# Proj15.net
KiCad netlist of a schematic drawn in EAGLE
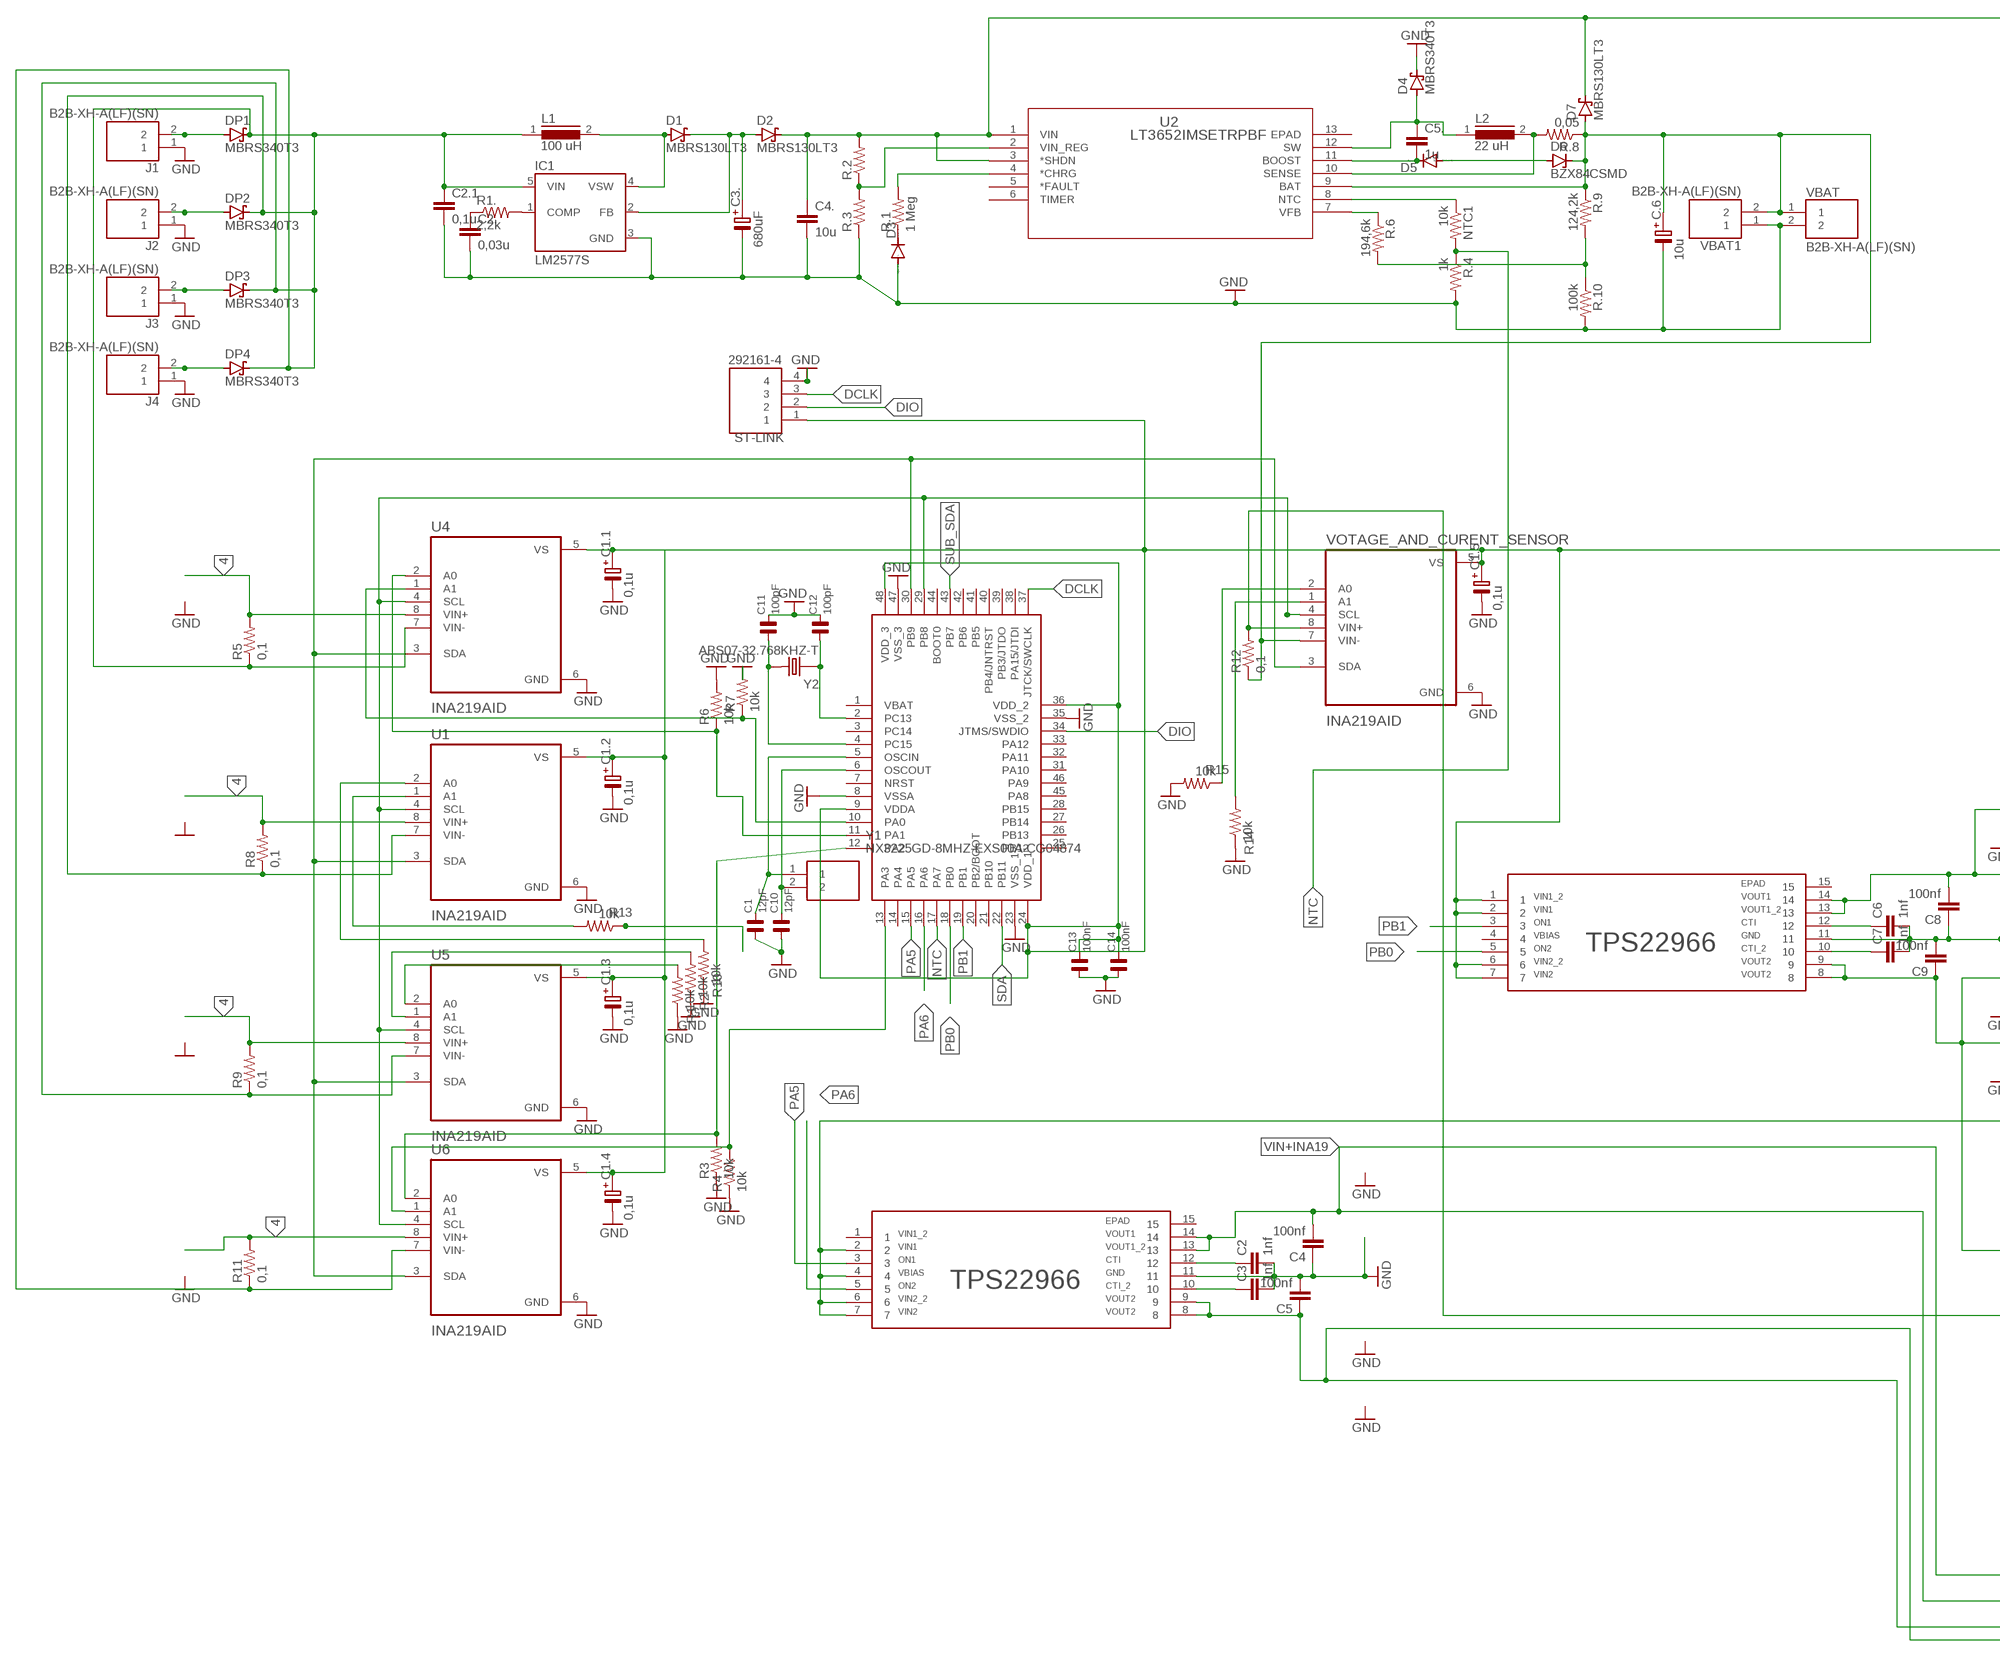
[diagram p0: schematic, sheet 1, part 1 of 2]
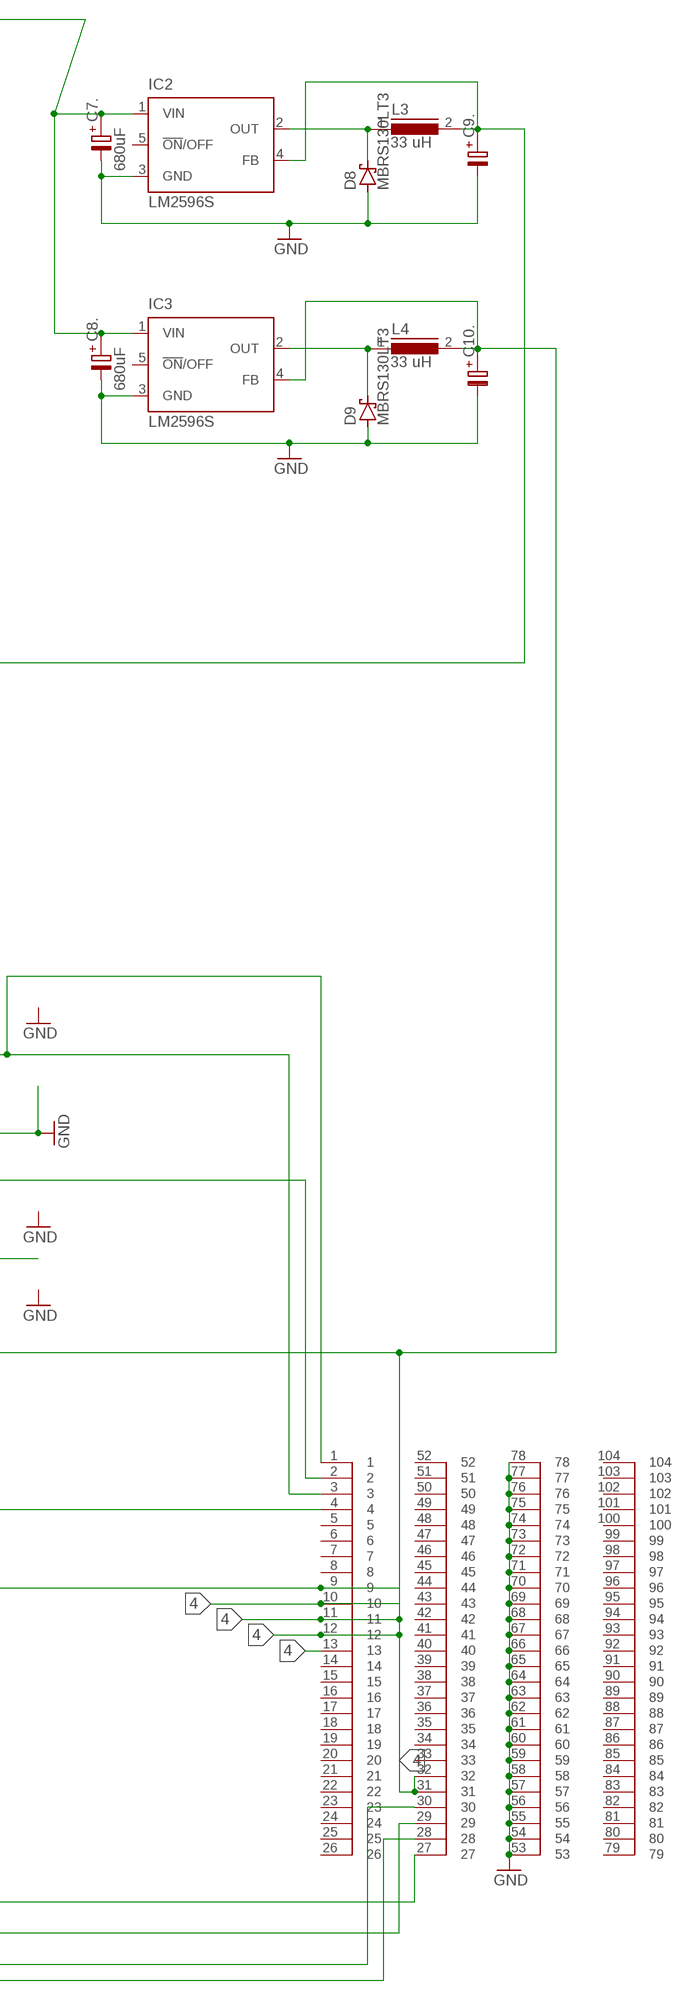
[diagram p1: schematic, sheet 1, part 2 of 2]

(export (version "E")
  (design (tool "Eeschema 10.0.6"))
  (components
    (comp (ref "C.6")
      (value "10u")
      (footprint "eagle-import:TE-D-7343")
      (libsource (lib "eagle-import") (part "C-PR-SMD-TE-D"))
    )
    (comp (ref "C1")
      (value "12pF")
      (footprint "eagle-import:0805")
      (libsource (lib "eagle-import") (part "C0805"))
    )
    (comp (ref "C1.1")
      (value "0,1u")
      (footprint "eagle-import:TE-D-7343")
      (libsource (lib "eagle-import") (part "C-PR-SMD-TE-D"))
    )
    (comp (ref "C1.2")
      (value "0,1u")
      (footprint "eagle-import:TE-D-7343")
      (libsource (lib "eagle-import") (part "C-PR-SMD-TE-D"))
    )
    (comp (ref "C1.3")
      (value "0,1u")
      (footprint "eagle-import:TE-D-7343")
      (libsource (lib "eagle-import") (part "C-PR-SMD-TE-D"))
    )
    (comp (ref "C1.4")
      (value "0,1u")
      (footprint "eagle-import:TE-D-7343")
      (libsource (lib "eagle-import") (part "C-PR-SMD-TE-D"))
    )
    (comp (ref "C1.5")
      (value "0,1u")
      (footprint "eagle-import:TE-D-7343")
      (libsource (lib "eagle-import") (part "C-PR-SMD-TE-D"))
    )
    (comp (ref "C2")
      (value "1nf")
      (footprint "eagle-import:C0805")
      (libsource (lib "eagle-import") (part "C-EUC0805"))
    )
    (comp (ref "C2.")
      (value "0,03u")
      (footprint "eagle-import:C1206")
      (libsource (lib "eagle-import") (part "C-EUC1206"))
    )
    (comp (ref "C2.1")
      (value "0,1u")
      (footprint "eagle-import:C1206")
      (libsource (lib "eagle-import") (part "C-EUC1206"))
    )
    (comp (ref "C3")
      (value "1nf")
      (footprint "eagle-import:C0805")
      (libsource (lib "eagle-import") (part "C-EUC0805"))
    )
    (comp (ref "C3.")
      (value "680uF")
      (footprint "eagle-import:TE-D-7343")
      (libsource (lib "eagle-import") (part "C-PR-SMD-TE-D"))
    )
    (comp (ref "C4")
      (value "100nf")
      (footprint "eagle-import:C0805")
      (libsource (lib "eagle-import") (part "C-EUC0805"))
    )
    (comp (ref "C4.")
      (value "10u")
      (footprint "eagle-import:C1206")
      (libsource (lib "eagle-import") (part "C-EUC1206"))
    )
    (comp (ref "C5")
      (value "100nf")
      (footprint "eagle-import:C0805")
      (libsource (lib "eagle-import") (part "C-EUC0805"))
    )
    (comp (ref "C5.")
      (value "1u")
      (footprint "eagle-import:C1206")
      (libsource (lib "eagle-import") (part "C-EUC1206"))
    )
    (comp (ref "C6")
      (value "1nf")
      (footprint "eagle-import:C0805")
      (libsource (lib "eagle-import") (part "C-EUC0805"))
    )
    (comp (ref "C7")
      (value "1nf")
      (footprint "eagle-import:C0805")
      (libsource (lib "eagle-import") (part "C-EUC0805"))
    )
    (comp (ref "C7.")
      (value "680uF")
      (footprint "eagle-import:TE-D-7343")
      (libsource (lib "eagle-import") (part "C-PR-SMD-TE-D"))
    )
    (comp (ref "C8")
      (value "100nf")
      (footprint "eagle-import:C0805")
      (libsource (lib "eagle-import") (part "C-EUC0805"))
    )
    (comp (ref "C8.")
      (value "680uF")
      (footprint "eagle-import:TE-D-7343")
      (libsource (lib "eagle-import") (part "C-PR-SMD-TE-D"))
    )
    (comp (ref "C9")
      (value "100nf")
      (footprint "eagle-import:C0805")
      (libsource (lib "eagle-import") (part "C-EUC0805"))
    )
    (comp (ref "C9.")
      (value "C-PR-SMD-TE-D")
      (footprint "eagle-import:TE-D-7343")
      (libsource (lib "eagle-import") (part "C-PR-SMD-TE-D"))
    )
    (comp (ref "C10")
      (value "12pF")
      (footprint "eagle-import:0805")
      (libsource (lib "eagle-import") (part "C0805"))
    )
    (comp (ref "C10.")
      (value "C-PR-SMD-TE-D")
      (footprint "eagle-import:TE-D-7343")
      (libsource (lib "eagle-import") (part "C-PR-SMD-TE-D"))
    )
    (comp (ref "C11")
      (value "100pF")
      (footprint "eagle-import:0805")
      (libsource (lib "eagle-import") (part "C0805"))
    )
    (comp (ref "C12")
      (value "100pF")
      (footprint "eagle-import:0805")
      (libsource (lib "eagle-import") (part "C0805"))
    )
    (comp (ref "C13")
      (value "100nF")
      (footprint "eagle-import:0805")
      (libsource (lib "eagle-import") (part "C0805"))
    )
    (comp (ref "C14")
      (value "100nF")
      (footprint "eagle-import:0805")
      (libsource (lib "eagle-import") (part "C0805"))
    )
    (comp (ref "D1")
      (value "MBRS130LT3")
      (footprint "eagle-import:SMB")
      (libsource (lib "eagle-import") (part "MBRS130LT3"))
    )
    (comp (ref "D2")
      (value "MBRS130LT3")
      (footprint "eagle-import:SMB")
      (libsource (lib "eagle-import") (part "MBRS130LT3"))
    )
    (comp (ref "D3")
      (value "DIODE-DO214BA")
      (footprint "eagle-import:DO214BA")
      (libsource (lib "eagle-import") (part "DIODE-DO214BA"))
    )
    (comp (ref "D4")
      (value "MBRS340T3")
      (footprint "eagle-import:SMC")
      (libsource (lib "eagle-import") (part "MBRS30T34"))
    )
    (comp (ref "D5")
      (value "DIODE-DO214BA")
      (footprint "eagle-import:DO214BA")
      (libsource (lib "eagle-import") (part "DIODE-DO214BA"))
    )
    (comp (ref "D6")
      (value "BZX84CSMD")
      (footprint "eagle-import:TO236")
      (libsource (lib "eagle-import") (part "BZX84CSMD"))
    )
    (comp (ref "D7")
      (value "MBRS130LT3")
      (footprint "eagle-import:SMB")
      (libsource (lib "eagle-import") (part "MBRS130LT3"))
    )
    (comp (ref "D8")
      (value "MBRS130LT3")
      (footprint "eagle-import:SMB")
      (libsource (lib "eagle-import") (part "MBRS130LT3"))
    )
    (comp (ref "D9")
      (value "MBRS130LT3")
      (footprint "eagle-import:SMB")
      (libsource (lib "eagle-import") (part "MBRS130LT3"))
    )
    (comp (ref "DP1")
      (value "MBRS340T3")
      (footprint "eagle-import:SMC")
      (libsource (lib "eagle-import") (part "MBRS30T34"))
    )
    (comp (ref "DP2")
      (value "MBRS340T3")
      (footprint "eagle-import:SMC")
      (libsource (lib "eagle-import") (part "MBRS30T34"))
    )
    (comp (ref "DP3")
      (value "MBRS340T3")
      (footprint "eagle-import:SMC")
      (libsource (lib "eagle-import") (part "MBRS30T34"))
    )
    (comp (ref "DP4")
      (value "MBRS340T3")
      (footprint "eagle-import:SMC")
      (libsource (lib "eagle-import") (part "MBRS30T34"))
    )
    (comp (ref "IC1")
      (value "LM2577S")
      (footprint "eagle-import:TO263-5")
      (libsource (lib "eagle-import") (part "LM2577S"))
    )
    (comp (ref "IC2")
      (value "LM2596S")
      (footprint "eagle-import:TO263-5")
      (fields (field (name "MF") "NATIONAL SEMICONDUCTOR") (field (name "MPN") "LM2596S-ADJ/NOPB"))
      (libsource (lib "eagle-import") (part "LM2596S"))
    )
    (comp (ref "IC3")
      (value "LM2596S")
      (footprint "eagle-import:TO263-5")
      (fields (field (name "MF") "NATIONAL SEMICONDUCTOR") (field (name "MPN") "LM2596S-ADJ/NOPB"))
      (libsource (lib "eagle-import") (part "LM2596S"))
    )
    (comp (ref "J1")
      (value "B2B-XH-A(LF)(SN)")
      (footprint "eagle-import:JST_B2B-XH-A(LF)(SN)")
      (fields (field (name "MF") "JST Sales"))
      (libsource (lib "eagle-import") (part "B2B-XH-A(LF)(SN)"))
    )
    (comp (ref "J2")
      (value "B2B-XH-A(LF)(SN)")
      (footprint "eagle-import:JST_B2B-XH-A(LF)(SN)")
      (fields (field (name "MF") "JST Sales"))
      (libsource (lib "eagle-import") (part "B2B-XH-A(LF)(SN)"))
    )
    (comp (ref "J3")
      (value "B2B-XH-A(LF)(SN)")
      (footprint "eagle-import:JST_B2B-XH-A(LF)(SN)")
      (fields (field (name "MF") "JST Sales"))
      (libsource (lib "eagle-import") (part "B2B-XH-A(LF)(SN)"))
    )
    (comp (ref "J4")
      (value "B2B-XH-A(LF)(SN)")
      (footprint "eagle-import:JST_B2B-XH-A(LF)(SN)")
      (fields (field (name "MF") "JST Sales"))
      (libsource (lib "eagle-import") (part "B2B-XH-A(LF)(SN)"))
    )
    (comp (ref "L1")
      (value "100 uH")
      (footprint "eagle-import:DR127")
      (libsource (lib "eagle-import") (part "DR127"))
    )
    (comp (ref "L2")
      (value "22 uH")
      (footprint "eagle-import:DR127")
      (libsource (lib "eagle-import") (part "DR127"))
    )
    (comp (ref "L3")
      (value "33 uH")
      (footprint "eagle-import:DR127")
      (libsource (lib "eagle-import") (part "DR127"))
    )
    (comp (ref "L4")
      (value "33 uH")
      (footprint "eagle-import:DR127")
      (libsource (lib "eagle-import") (part "DR127"))
    )
    (comp (ref "NTC1")
      (value "10k")
      (footprint "eagle-import:R0603")
      (libsource (lib "eagle-import") (part "R-US_R0603"))
    )
    (comp (ref "R.1")
      (value "1 Meg")
      (footprint "eagle-import:R3216")
      (libsource (lib "eagle-import") (part "R-US_R3216"))
    )
    (comp (ref "R.2")
      (value "R-US_R3216")
      (footprint "eagle-import:R3216")
      (libsource (lib "eagle-import") (part "R-US_R3216"))
    )
    (comp (ref "R.3")
      (value "R-US_R3216")
      (footprint "eagle-import:R3216")
      (libsource (lib "eagle-import") (part "R-US_R3216"))
    )
    (comp (ref "R.4")
      (value "1k")
      (footprint "eagle-import:R3216")
      (libsource (lib "eagle-import") (part "R-US_R3216"))
    )
    (comp (ref "R.6")
      (value "194,6k")
      (footprint "eagle-import:R3216")
      (libsource (lib "eagle-import") (part "R-US_R3216"))
    )
    (comp (ref "R.8")
      (value "0,05")
      (footprint "eagle-import:R3216")
      (libsource (lib "eagle-import") (part "R-US_R3216"))
    )
    (comp (ref "R.9")
      (value "124,2k")
      (footprint "eagle-import:R3216")
      (libsource (lib "eagle-import") (part "R-US_R3216"))
    )
    (comp (ref "R.10")
      (value "100k")
      (footprint "eagle-import:R3216")
      (libsource (lib "eagle-import") (part "R-US_R3216"))
    )
    (comp (ref "R1")
      (value "10k")
      (footprint "eagle-import:R3216")
      (libsource (lib "eagle-import") (part "R-US_R3216"))
    )
    (comp (ref "R1.")
      (value "2,2k")
      (footprint "eagle-import:R3216")
      (libsource (lib "eagle-import") (part "R-US_R3216"))
    )
    (comp (ref "R2")
      (value "10k")
      (footprint "eagle-import:R3216")
      (libsource (lib "eagle-import") (part "R-US_R3216"))
    )
    (comp (ref "R3")
      (value "10k")
      (footprint "eagle-import:R3216")
      (libsource (lib "eagle-import") (part "R-US_R3216"))
    )
    (comp (ref "R4")
      (value "10k")
      (footprint "eagle-import:R3216")
      (libsource (lib "eagle-import") (part "R-US_R3216"))
    )
    (comp (ref "R5")
      (value "0,1")
      (footprint "eagle-import:R3216")
      (libsource (lib "eagle-import") (part "R-US_R3216"))
    )
    (comp (ref "R6")
      (value "10k")
      (footprint "eagle-import:R3216")
      (libsource (lib "eagle-import") (part "R-US_R3216"))
    )
    (comp (ref "R7")
      (value "10k")
      (footprint "eagle-import:R3216")
      (libsource (lib "eagle-import") (part "R-US_R3216"))
    )
    (comp (ref "R8")
      (value "0,1")
      (footprint "eagle-import:R3216")
      (libsource (lib "eagle-import") (part "R-US_R3216"))
    )
    (comp (ref "R9")
      (value "0,1")
      (footprint "eagle-import:R3216")
      (libsource (lib "eagle-import") (part "R-US_R3216"))
    )
    (comp (ref "R10")
      (value "10k")
      (footprint "eagle-import:R3216")
      (libsource (lib "eagle-import") (part "R-US_R3216"))
    )
    (comp (ref "R11")
      (value "0,1")
      (footprint "eagle-import:R3216")
      (libsource (lib "eagle-import") (part "R-US_R3216"))
    )
    (comp (ref "R12")
      (value "0,1")
      (footprint "eagle-import:R3216")
      (libsource (lib "eagle-import") (part "R-US_R3216"))
    )
    (comp (ref "R13")
      (value "10k")
      (footprint "eagle-import:R3216")
      (libsource (lib "eagle-import") (part "R-US_R3216"))
    )
    (comp (ref "R14")
      (value "10k")
      (footprint "eagle-import:R3216")
      (libsource (lib "eagle-import") (part "R-US_R3216"))
    )
    (comp (ref "R15")
      (value "10k")
      (footprint "eagle-import:R3216")
      (libsource (lib "eagle-import") (part "R-US_R3216"))
    )
    (comp (ref "ST-LINK")
      (value "292161-4")
      (footprint "eagle-import:TE_292161-4")
      (fields (field (name "MF") "TE Connectivity"))
      (libsource (lib "eagle-import") (part "292161-4"))
    )
    (comp (ref "U$1")
      (value "TPS22966")
      (footprint "eagle-import:SON40P300X200X80-15N")
      (libsource (lib "eagle-import") (part "TPS22966"))
    )
    (comp (ref "U$2")
      (value "TPS22966")
      (footprint "eagle-import:SON40P300X200X80-15N")
      (libsource (lib "eagle-import") (part "TPS22966"))
    )
    (comp (ref "U$3")
      (value "HEADERPIN4X26")
      (footprint "eagle-import:HEADERPIN4X26")
      (libsource (lib "eagle-import") (part "HEADERPIN4X26"))
    )
    (comp (ref "U1")
      (value "INA219AID")
      (footprint "eagle-import:SOIC127P599X175-8N")
      (fields (field (name "MF") "Texas Instruments"))
      (libsource (lib "eagle-import") (part "INA219AID"))
    )
    (comp (ref "U2")
      (value "LT3652IMSETRPBF")
      (footprint "eagle-import:MSOP-12_MSE")
      (fields (field (name "MF") "Analog Devices") (field (name "MP") "LT3652IMSE#TRPBF"))
      (libsource (lib "eagle-import") (part "LT3652IMSETRPBF"))
    )
    (comp (ref "U3")
      (value "QFP50P900X900X160-48N")
      (footprint "eagle-import:QFP50P900X900X160-48N")
      (fields (field (name "MANUFACTURER") "STMicroelectronics"))
      (libsource (lib "eagle-import") (part "QFP50P900X900X160-48N"))
    )
    (comp (ref "U4")
      (value "INA219AID")
      (footprint "eagle-import:SOIC127P599X175-8N")
      (fields (field (name "MF") "Texas Instruments"))
      (libsource (lib "eagle-import") (part "INA219AID"))
    )
    (comp (ref "U5")
      (value "INA219AID")
      (footprint "eagle-import:SOIC127P599X175-8N")
      (fields (field (name "MF") "Texas Instruments"))
      (libsource (lib "eagle-import") (part "INA219AID"))
    )
    (comp (ref "U6")
      (value "INA219AID")
      (footprint "eagle-import:SOIC127P599X175-8N")
      (fields (field (name "MF") "Texas Instruments"))
      (libsource (lib "eagle-import") (part "INA219AID"))
    )
    (comp (ref "VBAT")
      (value "B2B-XH-A(LF)(SN)")
      (footprint "eagle-import:JST_B2B-XH-A(LF)(SN)")
      (fields (field (name "MF") "JST Sales"))
      (libsource (lib "eagle-import") (part "B2B-XH-A(LF)(SN)"))
    )
    (comp (ref "VBAT1")
      (value "B2B-XH-A(LF)(SN)")
      (footprint "eagle-import:JST_B2B-XH-A(LF)(SN)")
      (fields (field (name "MF") "JST Sales"))
      (libsource (lib "eagle-import") (part "B2B-XH-A(LF)(SN)"))
    )
    (comp (ref "VOTAGE_AND_CURENT_SENSOR")
      (value "INA219AID")
      (footprint "eagle-import:SOIC127P599X175-8N")
      (fields (field (name "MF") "Texas Instruments"))
      (libsource (lib "eagle-import") (part "INA219AID"))
    )
    (comp (ref "Y1")
      (value "NX3225GD-8MHZ-EXS00A-CG04874")
      (footprint "eagle-import:NX3225GD-STD-CRA-3")
      (libsource (lib "eagle-import") (part "NX3225GD-8MHZ-EXS00A-CG04874"))
    )
    (comp (ref "Y2")
      (value "ABS07-32.768KHZ-T")
      (footprint "eagle-import:XTAL_ABS07-32.768KHZ-T")
      (fields (field (name "MF") "Abracon"))
      (libsource (lib "eagle-import") (part "ABS07-32.768KHZ-T"))
    )
  )
  (nets
    (net (code "1") (name "4") (class "Default")
      (node (ref "C10.") (pin "+") (pinfunction "+_+") (pintype "passive"))
      (node (ref "IC3") (pin "4") (pinfunction "FB_4") (pintype "input"))
      (node (ref "L4") (pin "2") (pinfunction "2_2") (pintype "passive"))
      (node (ref "R11") (pin "2") (pinfunction "2_2") (pintype "passive"))
      (node (ref "R12") (pin "2") (pinfunction "2_2") (pintype "passive"))
      (node (ref "R5") (pin "2") (pinfunction "2_2") (pintype "passive"))
      (node (ref "R8") (pin "2") (pinfunction "2_2") (pintype "passive"))
      (node (ref "R9") (pin "2") (pinfunction "2_2") (pintype "passive"))
      (node (ref "U$1") (pin "2") (pinfunction "2_2") (pintype "bidirectional"))
      (node (ref "U$1") (pin "4") (pinfunction "4_4") (pintype "bidirectional"))
      (node (ref "U$1") (pin "6") (pinfunction "6_6") (pintype "bidirectional"))
      (node (ref "U$1") (pin "7") (pinfunction "7_7") (pintype "bidirectional"))
      (node (ref "U$3") (pin "10") (pinfunction "10_10") (pintype "bidirectional"))
      (node (ref "U$3") (pin "11") (pinfunction "11_11") (pintype "bidirectional"))
      (node (ref "U$3") (pin "12") (pinfunction "12_12") (pintype "bidirectional"))
      (node (ref "U$3") (pin "13") (pinfunction "13_13") (pintype "bidirectional"))
      (node (ref "U$3") (pin "31") (pinfunction "31_31") (pintype "bidirectional"))
      (node (ref "U$3") (pin "32") (pinfunction "32_32") (pintype "bidirectional"))
      (node (ref "U$3") (pin "9") (pinfunction "9_9") (pintype "bidirectional"))
      (node (ref "U1") (pin "8") (pinfunction "VIN+_8") (pintype "input"))
      (node (ref "U4") (pin "8") (pinfunction "VIN+_8") (pintype "input"))
      (node (ref "U5") (pin "8") (pinfunction "VIN+_8") (pintype "input"))
      (node (ref "U6") (pin "8") (pinfunction "VIN+_8") (pintype "input"))
      (node (ref "VOTAGE_AND_CURENT_SENSOR") (pin "8") (pinfunction "VIN+_8") (pintype "input"))
    )
    (net (code "2") (name "DCLK") (class "Default")
      (node (ref "ST-LINK") (pin "3") (pinfunction "3_3") (pintype "passive"))
      (node (ref "U3") (pin "37") (pinfunction "JTCK/SWCLK_37") (pintype "bidirectional"))
    )
    (net (code "3") (name "DIO") (class "Default")
      (node (ref "ST-LINK") (pin "2") (pinfunction "2_2") (pintype "passive"))
      (node (ref "U3") (pin "34") (pinfunction "JTMS/SWDIO_34") (pintype "bidirectional"))
    )
    (net (code "4") (name "GND") (class "Default")
      (node (ref "C.6") (pin "-") (pinfunction "-_-") (pintype "passive"))
      (node (ref "C1") (pin "1") (pinfunction "1_1") (pintype "passive"))
      (node (ref "C1.1") (pin "-") (pinfunction "-_-") (pintype "passive"))
      (node (ref "C1.2") (pin "-") (pinfunction "-_-") (pintype "passive"))
      (node (ref "C1.3") (pin "-") (pinfunction "-_-") (pintype "passive"))
      (node (ref "C1.4") (pin "-") (pinfunction "-_-") (pintype "passive"))
      (node (ref "C1.5") (pin "-") (pinfunction "-_-") (pintype "passive"))
      (node (ref "C10") (pin "1") (pinfunction "1_1") (pintype "passive"))
      (node (ref "C10.") (pin "-") (pinfunction "-_-") (pintype "passive"))
      (node (ref "C11") (pin "2") (pinfunction "2_2") (pintype "passive"))
      (node (ref "C12") (pin "2") (pinfunction "2_2") (pintype "passive"))
      (node (ref "C13") (pin "1") (pinfunction "1_1") (pintype "passive"))
      (node (ref "C14") (pin "1") (pinfunction "1_1") (pintype "passive"))
      (node (ref "C2") (pin "2") (pinfunction "2_2") (pintype "passive"))
      (node (ref "C2.") (pin "2") (pinfunction "2_2") (pintype "passive"))
      (node (ref "C2.1") (pin "2") (pinfunction "2_2") (pintype "passive"))
      (node (ref "C3") (pin "2") (pinfunction "2_2") (pintype "passive"))
      (node (ref "C3.") (pin "-") (pinfunction "-_-") (pintype "passive"))
      (node (ref "C4") (pin "1") (pinfunction "1_1") (pintype "passive"))
      (node (ref "C4.") (pin "2") (pinfunction "2_2") (pintype "passive"))
      (node (ref "C5") (pin "2") (pinfunction "2_2") (pintype "passive"))
      (node (ref "C6") (pin "2") (pinfunction "2_2") (pintype "passive"))
      (node (ref "C7") (pin "2") (pinfunction "2_2") (pintype "passive"))
      (node (ref "C7.") (pin "-") (pinfunction "-_-") (pintype "passive"))
      (node (ref "C8") (pin "1") (pinfunction "1_1") (pintype "passive"))
      (node (ref "C8.") (pin "-") (pinfunction "-_-") (pintype "passive"))
      (node (ref "C9") (pin "2") (pinfunction "2_2") (pintype "passive"))
      (node (ref "C9.") (pin "-") (pinfunction "-_-") (pintype "passive"))
      (node (ref "D3") (pin "A") (pinfunction "A_A") (pintype "passive"))
      (node (ref "D4") (pin "C") (pinfunction "C_C") (pintype "passive"))
      (node (ref "D8") (pin "A") (pinfunction "A_A") (pintype "passive"))
      (node (ref "D9") (pin "A") (pinfunction "A_A") (pintype "passive"))
      (node (ref "IC1") (pin "3") (pinfunction "GND_3") (pintype "power_in"))
      (node (ref "IC2") (pin "3") (pinfunction "GND_3") (pintype "power_in"))
      (node (ref "IC3") (pin "3") (pinfunction "GND_3") (pintype "power_in"))
      (node (ref "J1") (pin "1") (pinfunction "1_1") (pintype "passive"))
      (node (ref "J2") (pin "1") (pinfunction "1_1") (pintype "passive"))
      (node (ref "J3") (pin "1") (pinfunction "1_1") (pintype "passive"))
      (node (ref "J4") (pin "1") (pinfunction "1_1") (pintype "passive"))
      (node (ref "R.10") (pin "2") (pinfunction "2_2") (pintype "passive"))
      (node (ref "R.3") (pin "1") (pinfunction "1_1") (pintype "passive"))
      (node (ref "R.4") (pin "2") (pinfunction "2_2") (pintype "passive"))
      (node (ref "R1") (pin "1") (pinfunction "1_1") (pintype "passive"))
      (node (ref "R10") (pin "1") (pinfunction "1_1") (pintype "passive"))
      (node (ref "R14") (pin "1") (pinfunction "1_1") (pintype "passive"))
      (node (ref "R15") (pin "2") (pinfunction "2_2") (pintype "passive"))
      (node (ref "R2") (pin "1") (pinfunction "1_1") (pintype "passive"))
      (node (ref "R3") (pin "1") (pinfunction "1_1") (pintype "passive"))
      (node (ref "R4") (pin "1") (pinfunction "1_1") (pintype "passive"))
      (node (ref "R6") (pin "2") (pinfunction "2_2") (pintype "passive"))
      (node (ref "R7") (pin "2") (pinfunction "2_2") (pintype "passive"))
      (node (ref "ST-LINK") (pin "4") (pinfunction "4_4") (pintype "passive"))
      (node (ref "U$1") (pin "11") (pinfunction "11_11") (pintype "bidirectional"))
      (node (ref "U$2") (pin "11") (pinfunction "11_11") (pintype "bidirectional"))
      (node (ref "U$3") (pin "53") (pinfunction "53_53") (pintype "bidirectional"))
      (node (ref "U$3") (pin "54") (pinfunction "54_54") (pintype "bidirectional"))
      (node (ref "U$3") (pin "55") (pinfunction "55_55") (pintype "bidirectional"))
      (node (ref "U$3") (pin "56") (pinfunction "56_56") (pintype "bidirectional"))
      (node (ref "U$3") (pin "57") (pinfunction "57_57") (pintype "bidirectional"))
      (node (ref "U$3") (pin "58") (pinfunction "58_58") (pintype "bidirectional"))
      (node (ref "U$3") (pin "59") (pinfunction "59_59") (pintype "bidirectional"))
      (node (ref "U$3") (pin "60") (pinfunction "60_60") (pintype "bidirectional"))
      (node (ref "U$3") (pin "61") (pinfunction "61_61") (pintype "bidirectional"))
      (node (ref "U$3") (pin "62") (pinfunction "62_62") (pintype "bidirectional"))
      (node (ref "U$3") (pin "63") (pinfunction "63_63") (pintype "bidirectional"))
      (node (ref "U$3") (pin "64") (pinfunction "64_64") (pintype "bidirectional"))
      (node (ref "U$3") (pin "65") (pinfunction "65_65") (pintype "bidirectional"))
      (node (ref "U$3") (pin "66") (pinfunction "66_66") (pintype "bidirectional"))
      (node (ref "U$3") (pin "67") (pinfunction "67_67") (pintype "bidirectional"))
      (node (ref "U$3") (pin "68") (pinfunction "68_68") (pintype "bidirectional"))
      (node (ref "U$3") (pin "69") (pinfunction "69_69") (pintype "bidirectional"))
      (node (ref "U$3") (pin "70") (pinfunction "70_70") (pintype "bidirectional"))
      (node (ref "U$3") (pin "71") (pinfunction "71_71") (pintype "bidirectional"))
      (node (ref "U$3") (pin "72") (pinfunction "72_72") (pintype "bidirectional"))
      (node (ref "U$3") (pin "73") (pinfunction "73_73") (pintype "bidirectional"))
      (node (ref "U$3") (pin "74") (pinfunction "74_74") (pintype "bidirectional"))
      (node (ref "U$3") (pin "75") (pinfunction "75_75") (pintype "bidirectional"))
      (node (ref "U$3") (pin "76") (pinfunction "76_76") (pintype "bidirectional"))
      (node (ref "U$3") (pin "77") (pinfunction "77_77") (pintype "bidirectional"))
      (node (ref "U$3") (pin "78") (pinfunction "78_78") (pintype "bidirectional"))
      (node (ref "U1") (pin "6") (pinfunction "GND_6") (pintype "power_in"))
      (node (ref "U3") (pin "23") (pinfunction "VSS_1_23") (pintype "bidirectional"))
      (node (ref "U3") (pin "35") (pinfunction "VSS_2_35") (pintype "bidirectional"))
      (node (ref "U3") (pin "47") (pinfunction "VSS_3_47") (pintype "bidirectional"))
      (node (ref "U3") (pin "8") (pinfunction "VSSA_8") (pintype "bidirectional"))
      (node (ref "U4") (pin "6") (pinfunction "GND_6") (pintype "power_in"))
      (node (ref "U5") (pin "6") (pinfunction "GND_6") (pintype "power_in"))
      (node (ref "U6") (pin "6") (pinfunction "GND_6") (pintype "power_in"))
      (node (ref "VBAT") (pin "2") (pinfunction "2_2") (pintype "passive"))
      (node (ref "VBAT1") (pin "1") (pinfunction "1_1") (pintype "passive"))
      (node (ref "VOTAGE_AND_CURENT_SENSOR") (pin "6") (pinfunction "GND_6") (pintype "power_in"))
    )
    (net (code "5") (name "NTC") (class "Default")
      (node (ref "NTC1") (pin "2") (pinfunction "2_2") (pintype "passive"))
      (node (ref "R.4") (pin "1") (pinfunction "1_1") (pintype "passive"))
      (node (ref "R14") (pin "2") (pinfunction "2_2") (pintype "passive"))
      (node (ref "U3") (pin "17") (pinfunction "PA7_17") (pintype "bidirectional"))
      (node (ref "VOTAGE_AND_CURENT_SENSOR") (pin "1") (pinfunction "A1_1") (pintype "input"))
    )
    (net (code "6") (name "Net-(C2-Pad1)") (class "Default")
      (node (ref "C2") (pin "1") (pinfunction "1_1") (pintype "passive"))
      (node (ref "U$1") (pin "12") (pinfunction "12_12") (pintype "bidirectional"))
    )
    (net (code "7") (name "Net-(C2.-Pad1)") (class "Default")
      (node (ref "C2.") (pin "1") (pinfunction "1_1") (pintype "passive"))
      (node (ref "R1.") (pin "1") (pinfunction "1_1") (pintype "passive"))
    )
    (net (code "8") (name "Net-(C3-Pad1)") (class "Default")
      (node (ref "C3") (pin "1") (pinfunction "1_1") (pintype "passive"))
      (node (ref "U$1") (pin "10") (pinfunction "10_10") (pintype "bidirectional"))
    )
    (net (code "9") (name "Net-(C5-Pad1)") (class "Default")
      (node (ref "C5") (pin "1") (pinfunction "1_1") (pintype "passive"))
      (node (ref "U$1") (pin "8") (pinfunction "8_8") (pintype "bidirectional"))
      (node (ref "U$1") (pin "9") (pinfunction "9_9") (pintype "bidirectional"))
      (node (ref "U$3") (pin "28") (pinfunction "28_28") (pintype "bidirectional"))
      (node (ref "U$3") (pin "30") (pinfunction "30_30") (pintype "bidirectional"))
    )
    (net (code "10") (name "Net-(C6-Pad1)") (class "Default")
      (node (ref "C6") (pin "1") (pinfunction "1_1") (pintype "passive"))
      (node (ref "U$2") (pin "12") (pinfunction "12_12") (pintype "bidirectional"))
    )
    (net (code "11") (name "Net-(C7-Pad1)") (class "Default")
      (node (ref "C7") (pin "1") (pinfunction "1_1") (pintype "passive"))
      (node (ref "U$2") (pin "10") (pinfunction "10_10") (pintype "bidirectional"))
    )
    (net (code "12") (name "Net-(C8-Pad2)") (class "Default")
      (node (ref "C8") (pin "2") (pinfunction "2_2") (pintype "passive"))
      (node (ref "U$2") (pin "13") (pinfunction "13_13") (pintype "bidirectional"))
      (node (ref "U$2") (pin "14") (pinfunction "14_14") (pintype "bidirectional"))
      (node (ref "U$3") (pin "1") (pinfunction "1_1") (pintype "bidirectional"))
      (node (ref "U$3") (pin "3") (pinfunction "3_3") (pintype "bidirectional"))
    )
    (net (code "13") (name "Net-(C9-Pad1)") (class "Default")
      (node (ref "C9") (pin "1") (pinfunction "1_1") (pintype "passive"))
      (node (ref "U$2") (pin "8") (pinfunction "8_8") (pintype "bidirectional"))
      (node (ref "U$2") (pin "9") (pinfunction "9_9") (pintype "bidirectional"))
      (node (ref "U$3") (pin "2") (pinfunction "2_2") (pintype "bidirectional"))
      (node (ref "U$3") (pin "4") (pinfunction "4_4") (pintype "bidirectional"))
    )
    (net (code "14") (name "Net-(D3-PadC)") (class "Default")
      (node (ref "D3") (pin "C") (pinfunction "C_C") (pintype "passive"))
      (node (ref "R.1") (pin "1") (pinfunction "1_1") (pintype "passive"))
    )
    (net (code "15") (name "Net-(D5-PadA)") (class "Default")
      (node (ref "D5") (pin "A") (pinfunction "A_A") (pintype "passive"))
      (node (ref "D6") (pin "A") (pinfunction "A_A") (pintype "passive"))
    )
    (net (code "16") (name "Net-(DP1-PadA)") (class "Default")
      (node (ref "DP1") (pin "A") (pinfunction "A_A") (pintype "passive"))
      (node (ref "J1") (pin "2") (pinfunction "2_2") (pintype "passive"))
    )
    (net (code "17") (name "Net-(DP2-PadA)") (class "Default")
      (node (ref "DP2") (pin "A") (pinfunction "A_A") (pintype "passive"))
      (node (ref "J2") (pin "2") (pinfunction "2_2") (pintype "passive"))
    )
    (net (code "18") (name "Net-(DP3-PadA)") (class "Default")
      (node (ref "DP3") (pin "A") (pinfunction "A_A") (pintype "passive"))
      (node (ref "J3") (pin "2") (pinfunction "2_2") (pintype "passive"))
    )
    (net (code "19") (name "Net-(DP4-PadA)") (class "Default")
      (node (ref "DP4") (pin "A") (pinfunction "A_A") (pintype "passive"))
      (node (ref "J4") (pin "2") (pinfunction "2_2") (pintype "passive"))
    )
    (net (code "20") (name "Net-(IC1-COMP)") (class "Default")
      (node (ref "IC1") (pin "1") (pinfunction "COMP_1") (pintype "passive"))
      (node (ref "R1.") (pin "2") (pinfunction "2_2") (pintype "passive"))
    )
    (net (code "21") (name "Net-(IC1-FB)") (class "Default")
      (node (ref "C3.") (pin "+") (pinfunction "+_+") (pintype "passive"))
      (node (ref "D1") (pin "C") (pinfunction "C_C") (pintype "passive"))
      (node (ref "D2") (pin "A") (pinfunction "A_A") (pintype "passive"))
      (node (ref "IC1") (pin "2") (pinfunction "FB_2") (pintype "input"))
    )
    (net (code "22") (name "Net-(IC1-VIN)") (class "Default")
      (node (ref "C2.1") (pin "1") (pinfunction "1_1") (pintype "passive"))
      (node (ref "DP1") (pin "C") (pinfunction "C_C") (pintype "passive"))
      (node (ref "DP2") (pin "C") (pinfunction "C_C") (pintype "passive"))
      (node (ref "DP3") (pin "C") (pinfunction "C_C") (pintype "passive"))
      (node (ref "DP4") (pin "C") (pinfunction "C_C") (pintype "passive"))
      (node (ref "IC1") (pin "5") (pinfunction "VIN_5") (pintype "power_in"))
      (node (ref "L1") (pin "1") (pinfunction "1_1") (pintype "passive"))
      (node (ref "R11") (pin "1") (pinfunction "1_1") (pintype "passive"))
      (node (ref "R5") (pin "1") (pinfunction "1_1") (pintype "passive"))
      (node (ref "R8") (pin "1") (pinfunction "1_1") (pintype "passive"))
      (node (ref "R9") (pin "1") (pinfunction "1_1") (pintype "passive"))
      (node (ref "U1") (pin "7") (pinfunction "VIN-_7") (pintype "input"))
      (node (ref "U4") (pin "7") (pinfunction "VIN-_7") (pintype "input"))
      (node (ref "U5") (pin "7") (pinfunction "VIN-_7") (pintype "input"))
      (node (ref "U6") (pin "7") (pinfunction "VIN-_7") (pintype "input"))
    )
    (net (code "23") (name "Net-(IC1-VSW)") (class "Default")
      (node (ref "D1") (pin "A") (pinfunction "A_A") (pintype "passive"))
      (node (ref "IC1") (pin "4") (pinfunction "VSW_4") (pintype "bidirectional"))
      (node (ref "L1") (pin "2") (pinfunction "2_2") (pintype "passive"))
    )
    (net (code "24") (name "Net-(IC2-FB)") (class "Default")
      (node (ref "C1.1") (pin "+") (pinfunction "+_+") (pintype "passive"))
      (node (ref "C1.2") (pin "+") (pinfunction "+_+") (pintype "passive"))
      (node (ref "C1.3") (pin "+") (pinfunction "+_+") (pintype "passive"))
      (node (ref "C1.4") (pin "+") (pinfunction "+_+") (pintype "passive"))
      (node (ref "C1.5") (pin "+") (pinfunction "+_+") (pintype "passive"))
      (node (ref "C13") (pin "2") (pinfunction "2_2") (pintype "passive"))
      (node (ref "C14") (pin "2") (pinfunction "2_2") (pintype "passive"))
      (node (ref "C9.") (pin "+") (pinfunction "+_+") (pintype "passive"))
      (node (ref "IC2") (pin "4") (pinfunction "FB_4") (pintype "input"))
      (node (ref "L3") (pin "2") (pinfunction "2_2") (pintype "passive"))
      (node (ref "ST-LINK") (pin "1") (pinfunction "1_1") (pintype "passive"))
      (node (ref "U$2") (pin "1") (pinfunction "1_1") (pintype "bidirectional"))
      (node (ref "U$2") (pin "2") (pinfunction "2_2") (pintype "bidirectional"))
      (node (ref "U$2") (pin "6") (pinfunction "6_6") (pintype "bidirectional"))
      (node (ref "U$2") (pin "7") (pinfunction "7_7") (pintype "bidirectional"))
      (node (ref "U1") (pin "5") (pinfunction "VS_5") (pintype "power_in"))
      (node (ref "U3") (pin "24") (pinfunction "VDD_1_24") (pintype "bidirectional"))
      (node (ref "U3") (pin "36") (pinfunction "VDD_2_36") (pintype "bidirectional"))
      (node (ref "U3") (pin "48") (pinfunction "VDD_3_48") (pintype "bidirectional"))
      (node (ref "U3") (pin "9") (pinfunction "VDDA_9") (pintype "bidirectional"))
      (node (ref "U4") (pin "5") (pinfunction "VS_5") (pintype "power_in"))
      (node (ref "U5") (pin "5") (pinfunction "VS_5") (pintype "power_in"))
      (node (ref "U6") (pin "5") (pinfunction "VS_5") (pintype "power_in"))
      (node (ref "VOTAGE_AND_CURENT_SENSOR") (pin "5") (pinfunction "VS_5") (pintype "power_in"))
    )
    (net (code "25") (name "Net-(IC2-OUT)") (class "Default")
      (node (ref "D8") (pin "C") (pinfunction "C_C") (pintype "passive"))
      (node (ref "IC2") (pin "2") (pinfunction "OUT_2") (pintype "output"))
      (node (ref "L3") (pin "1") (pinfunction "1_1") (pintype "passive"))
    )
    (net (code "26") (name "Net-(IC2-VIN)") (class "Default")
      (node (ref "C4.") (pin "1") (pinfunction "1_1") (pintype "passive"))
      (node (ref "C7.") (pin "+") (pinfunction "+_+") (pintype "passive"))
      (node (ref "C8.") (pin "+") (pinfunction "+_+") (pintype "passive"))
      (node (ref "D2") (pin "C") (pinfunction "C_C") (pintype "passive"))
      (node (ref "D7") (pin "C") (pinfunction "C_C") (pintype "passive"))
      (node (ref "IC2") (pin "1") (pinfunction "VIN_1") (pintype "input"))
      (node (ref "IC3") (pin "1") (pinfunction "VIN_1") (pintype "input"))
      (node (ref "R.2") (pin "2") (pinfunction "2_2") (pintype "passive"))
      (node (ref "U2") (pin "1") (pinfunction "VIN_1") (pintype "input"))
      (node (ref "U2") (pin "3") (pinfunction "*SHDN_3") (pintype "input"))
    )
    (net (code "27") (name "Net-(IC3-OUT)") (class "Default")
      (node (ref "D9") (pin "C") (pinfunction "C_C") (pintype "passive"))
      (node (ref "IC3") (pin "2") (pinfunction "OUT_2") (pintype "output"))
      (node (ref "L4") (pin "1") (pinfunction "1_1") (pintype "passive"))
    )
    (net (code "28") (name "Net-(R.10-Pad1)") (class "Default")
      (node (ref "R.10") (pin "1") (pinfunction "1_1") (pintype "passive"))
      (node (ref "R.6") (pin "2") (pinfunction "2_2") (pintype "passive"))
      (node (ref "R.9") (pin "2") (pinfunction "2_2") (pintype "passive"))
    )
    (net (code "29") (name "Net-(U1-A0)") (class "Default")
      (node (ref "R10") (pin "2") (pinfunction "2_2") (pintype "passive"))
      (node (ref "U1") (pin "2") (pinfunction "A0_2") (pintype "input"))
    )
    (net (code "30") (name "Net-(U1-A1)") (class "Default")
      (node (ref "R13") (pin "2") (pinfunction "2_2") (pintype "passive"))
      (node (ref "U1") (pin "1") (pinfunction "A1_1") (pintype "input"))
    )
    (net (code "31") (name "Net-(U1-SCL)") (class "Default")
      (node (ref "U1") (pin "4") (pinfunction "SCL_4") (pintype "input"))
      (node (ref "U3") (pin "29") (pinfunction "PB8_29") (pintype "bidirectional"))
      (node (ref "U4") (pin "4") (pinfunction "SCL_4") (pintype "input"))
      (node (ref "U5") (pin "4") (pinfunction "SCL_4") (pintype "input"))
      (node (ref "U6") (pin "4") (pinfunction "SCL_4") (pintype "input"))
      (node (ref "VOTAGE_AND_CURENT_SENSOR") (pin "4") (pinfunction "SCL_4") (pintype "input"))
    )
    (net (code "32") (name "Net-(U1-SDA)") (class "Default")
      (node (ref "U1") (pin "3") (pinfunction "SDA_3") (pintype "bidirectional"))
      (node (ref "U3") (pin "30") (pinfunction "PB9_30") (pintype "bidirectional"))
      (node (ref "U4") (pin "3") (pinfunction "SDA_3") (pintype "bidirectional"))
      (node (ref "U5") (pin "3") (pinfunction "SDA_3") (pintype "bidirectional"))
      (node (ref "U6") (pin "3") (pinfunction "SDA_3") (pintype "bidirectional"))
      (node (ref "VOTAGE_AND_CURENT_SENSOR") (pin "3") (pinfunction "SDA_3") (pintype "bidirectional"))
    )
    (net (code "33") (name "Net-(U2-*CHRG)") (class "Default")
      (node (ref "R.1") (pin "2") (pinfunction "2_2") (pintype "passive"))
      (node (ref "U2") (pin "4") (pinfunction "*CHRG_4") (pintype "output"))
    )
    (net (code "34") (name "Net-(U2-BAT)") (class "Default")
      (node (ref "C.6") (pin "+") (pinfunction "+_+") (pintype "passive"))
      (node (ref "D6") (pin "C") (pinfunction "C_C") (pintype "passive"))
      (node (ref "D7") (pin "A") (pinfunction "A_A") (pintype "passive"))
      (node (ref "R.8") (pin "1") (pinfunction "1_1") (pintype "passive"))
      (node (ref "R.9") (pin "1") (pinfunction "1_1") (pintype "passive"))
      (node (ref "R12") (pin "1") (pinfunction "1_1") (pintype "passive"))
      (node (ref "U2") (pin "9") (pinfunction "BAT_9") (pintype "output"))
      (node (ref "VBAT") (pin "1") (pinfunction "1_1") (pintype "passive"))
      (node (ref "VBAT1") (pin "2") (pinfunction "2_2") (pintype "passive"))
      (node (ref "VOTAGE_AND_CURENT_SENSOR") (pin "7") (pinfunction "VIN-_7") (pintype "input"))
    )
    (net (code "35") (name "Net-(U2-BOOST)") (class "Default")
      (node (ref "C5.") (pin "2") (pinfunction "2_2") (pintype "passive"))
      (node (ref "D5") (pin "C") (pinfunction "C_C") (pintype "passive"))
      (node (ref "U2") (pin "11") (pinfunction "BOOST_11") (pintype "passive"))
    )
    (net (code "36") (name "Net-(U2-NTC)") (class "Default")
      (node (ref "NTC1") (pin "1") (pinfunction "1_1") (pintype "passive"))
      (node (ref "U2") (pin "8") (pinfunction "NTC_8") (pintype "input"))
    )
    (net (code "37") (name "Net-(U2-SENSE)") (class "Default")
      (node (ref "L2") (pin "2") (pinfunction "2_2") (pintype "passive"))
      (node (ref "R.8") (pin "2") (pinfunction "2_2") (pintype "passive"))
      (node (ref "U2") (pin "10") (pinfunction "SENSE_10") (pintype "passive"))
    )
    (net (code "38") (name "Net-(U2-SW)") (class "Default")
      (node (ref "C5.") (pin "1") (pinfunction "1_1") (pintype "passive"))
      (node (ref "D4") (pin "A") (pinfunction "A_A") (pintype "passive"))
      (node (ref "L2") (pin "1") (pinfunction "1_1") (pintype "passive"))
      (node (ref "U2") (pin "12") (pinfunction "SW_12") (pintype "output"))
    )
    (net (code "39") (name "Net-(U2-VFB)") (class "Default")
      (node (ref "R.6") (pin "1") (pinfunction "1_1") (pintype "passive"))
      (node (ref "U2") (pin "7") (pinfunction "VFB_7") (pintype "output"))
    )
    (net (code "40") (name "Net-(U2-VIN_REG)") (class "Default")
      (node (ref "R.2") (pin "1") (pinfunction "1_1") (pintype "passive"))
      (node (ref "R.3") (pin "2") (pinfunction "2_2") (pintype "passive"))
      (node (ref "U2") (pin "2") (pinfunction "VIN_REG_2") (pintype "input"))
    )
    (net (code "41") (name "Net-(U3-OSCIN)") (class "Default")
      (node (ref "C1") (pin "2") (pinfunction "2_2") (pintype "passive"))
      (node (ref "U3") (pin "5") (pinfunction "OSCIN_5") (pintype "bidirectional"))
      (node (ref "Y1") (pin "1") (pinfunction "1_1") (pintype "bidirectional"))
    )
    (net (code "42") (name "Net-(U3-OSCOUT)") (class "Default")
      (node (ref "C10") (pin "2") (pinfunction "2_2") (pintype "passive"))
      (node (ref "U3") (pin "6") (pinfunction "OSCOUT_6") (pintype "bidirectional"))
      (node (ref "Y1") (pin "2") (pinfunction "2_2") (pintype "bidirectional"))
    )
    (net (code "43") (name "Net-(U3-PA0)") (class "Default")
      (node (ref "R7") (pin "1") (pinfunction "1_1") (pintype "passive"))
      (node (ref "U3") (pin "10") (pinfunction "PA0_10") (pintype "bidirectional"))
      (node (ref "U4") (pin "1") (pinfunction "A1_1") (pintype "input"))
    )
    (net (code "44") (name "Net-(U3-PA1)") (class "Default")
      (node (ref "R6") (pin "1") (pinfunction "1_1") (pintype "passive"))
      (node (ref "U3") (pin "11") (pinfunction "PA1_11") (pintype "bidirectional"))
      (node (ref "U4") (pin "2") (pinfunction "A0_2") (pintype "input"))
    )
    (net (code "45") (name "Net-(U3-PA2)") (class "Default")
      (node (ref "R3") (pin "2") (pinfunction "2_2") (pintype "passive"))
      (node (ref "U3") (pin "12") (pinfunction "PA2_12") (pintype "bidirectional"))
      (node (ref "U6") (pin "2") (pinfunction "A0_2") (pintype "input"))
    )
    (net (code "46") (name "Net-(U3-PA3)") (class "Default")
      (node (ref "R4") (pin "2") (pinfunction "2_2") (pintype "passive"))
      (node (ref "U3") (pin "13") (pinfunction "PA3_13") (pintype "bidirectional"))
      (node (ref "U6") (pin "1") (pinfunction "A1_1") (pintype "input"))
    )
    (net (code "47") (name "Net-(U3-PC13)") (class "Default")
      (node (ref "C12") (pin "1") (pinfunction "1_1") (pintype "passive"))
      (node (ref "U3") (pin "2") (pinfunction "PC13_2") (pintype "bidirectional"))
      (node (ref "Y2") (pin "1") (pinfunction "1_1") (pintype "passive"))
    )
    (net (code "48") (name "Net-(U3-PC15)") (class "Default")
      (node (ref "C11") (pin "1") (pinfunction "1_1") (pintype "passive"))
      (node (ref "U3") (pin "4") (pinfunction "PC15_4") (pintype "bidirectional"))
      (node (ref "Y2") (pin "2") (pinfunction "2_2") (pintype "passive"))
    )
    (net (code "49") (name "Net-(U5-A0)") (class "Default")
      (node (ref "R1") (pin "2") (pinfunction "2_2") (pintype "passive"))
      (node (ref "U5") (pin "2") (pinfunction "A0_2") (pintype "input"))
    )
    (net (code "50") (name "Net-(U5-A1)") (class "Default")
      (node (ref "R2") (pin "2") (pinfunction "2_2") (pintype "passive"))
      (node (ref "U5") (pin "1") (pinfunction "A1_1") (pintype "input"))
    )
    (net (code "51") (name "Net-(VOTAGE_AND_CURENT_SENSOR-A0)") (class "Default")
      (node (ref "R15") (pin "1") (pinfunction "1_1") (pintype "passive"))
      (node (ref "VOTAGE_AND_CURENT_SENSOR") (pin "2") (pinfunction "A0_2") (pintype "input"))
    )
    (net (code "52") (name "PA5") (class "Default")
      (node (ref "U$1") (pin "3") (pinfunction "3_3") (pintype "bidirectional"))
      (node (ref "U3") (pin "15") (pinfunction "PA5_15") (pintype "bidirectional"))
    )
    (net (code "53") (name "PA6") (class "Default")
      (node (ref "U$1") (pin "5") (pinfunction "5_5") (pintype "bidirectional"))
      (node (ref "U3") (pin "16") (pinfunction "PA6_16") (pintype "bidirectional"))
    )
    (net (code "54") (name "PB0") (class "Default")
      (node (ref "U$2") (pin "5") (pinfunction "5_5") (pintype "bidirectional"))
      (node (ref "U3") (pin "18") (pinfunction "PB0_18") (pintype "bidirectional"))
    )
    (net (code "55") (name "PB1") (class "Default")
      (node (ref "U$2") (pin "3") (pinfunction "3_3") (pintype "bidirectional"))
      (node (ref "U3") (pin "19") (pinfunction "PB1_19") (pintype "bidirectional"))
    )
    (net (code "56") (name "SDA") (class "Default")
      (node (ref "U3") (pin "22") (pinfunction "PB11_22") (pintype "bidirectional"))
    )
    (net (code "57") (name "SUB_SDA") (class "Default")
      (node (ref "U3") (pin "43") (pinfunction "PB7_43") (pintype "bidirectional"))
    )
    (net (code "58") (name "VIN+INA19") (class "Default")
      (node (ref "C4") (pin "2") (pinfunction "2_2") (pintype "passive"))
      (node (ref "U$1") (pin "13") (pinfunction "13_13") (pintype "bidirectional"))
      (node (ref "U$1") (pin "14") (pinfunction "14_14") (pintype "bidirectional"))
      (node (ref "U$3") (pin "27") (pinfunction "27_27") (pintype "bidirectional"))
      (node (ref "U$3") (pin "29") (pinfunction "29_29") (pintype "bidirectional"))
    )
    (net (code "59") (name "unconnected-(IC2-~{ON}{slash}OFF-Pad5)") (class "Default")
      (node (ref "IC2") (pin "5") (pinfunction "~{ON}/OFF_5") (pintype "input"))
    )
    (net (code "60") (name "unconnected-(IC3-~{ON}{slash}OFF-Pad5)") (class "Default")
      (node (ref "IC3") (pin "5") (pinfunction "~{ON}/OFF_5") (pintype "input"))
    )
    (net (code "61") (name "unconnected-(R13-Pad1)") (class "Default")
      (node (ref "R13") (pin "1") (pinfunction "1_1") (pintype "passive"))
    )
    (net (code "62") (name "unconnected-(U$1-Pad1)") (class "Default")
      (node (ref "U$1") (pin "1") (pinfunction "1_1") (pintype "bidirectional"))
    )
    (net (code "63") (name "unconnected-(U$1-Pad15)") (class "Default")
      (node (ref "U$1") (pin "15") (pinfunction "15_15") (pintype "bidirectional"))
    )
    (net (code "64") (name "unconnected-(U$2-Pad4)") (class "Default")
      (node (ref "U$2") (pin "4") (pinfunction "4_4") (pintype "bidirectional"))
    )
    (net (code "65") (name "unconnected-(U$2-Pad15)") (class "Default")
      (node (ref "U$2") (pin "15") (pinfunction "15_15") (pintype "bidirectional"))
    )
    (net (code "66") (name "unconnected-(U$3-Pad5)") (class "Default")
      (node (ref "U$3") (pin "5") (pinfunction "5_5") (pintype "bidirectional"))
    )
    (net (code "67") (name "unconnected-(U$3-Pad6)") (class "Default")
      (node (ref "U$3") (pin "6") (pinfunction "6_6") (pintype "bidirectional"))
    )
    (net (code "68") (name "unconnected-(U$3-Pad7)") (class "Default")
      (node (ref "U$3") (pin "7") (pinfunction "7_7") (pintype "bidirectional"))
    )
    (net (code "69") (name "unconnected-(U$3-Pad8)") (class "Default")
      (node (ref "U$3") (pin "8") (pinfunction "8_8") (pintype "bidirectional"))
    )
    (net (code "70") (name "unconnected-(U$3-Pad14)") (class "Default")
      (node (ref "U$3") (pin "14") (pinfunction "14_14") (pintype "bidirectional"))
    )
    (net (code "71") (name "unconnected-(U$3-Pad15)") (class "Default")
      (node (ref "U$3") (pin "15") (pinfunction "15_15") (pintype "bidirectional"))
    )
    (net (code "72") (name "unconnected-(U$3-Pad16)") (class "Default")
      (node (ref "U$3") (pin "16") (pinfunction "16_16") (pintype "bidirectional"))
    )
    (net (code "73") (name "unconnected-(U$3-Pad17)") (class "Default")
      (node (ref "U$3") (pin "17") (pinfunction "17_17") (pintype "bidirectional"))
    )
    (net (code "74") (name "unconnected-(U$3-Pad18)") (class "Default")
      (node (ref "U$3") (pin "18") (pinfunction "18_18") (pintype "bidirectional"))
    )
    (net (code "75") (name "unconnected-(U$3-Pad19)") (class "Default")
      (node (ref "U$3") (pin "19") (pinfunction "19_19") (pintype "bidirectional"))
    )
    (net (code "76") (name "unconnected-(U$3-Pad20)") (class "Default")
      (node (ref "U$3") (pin "20") (pinfunction "20_20") (pintype "bidirectional"))
    )
    (net (code "77") (name "unconnected-(U$3-Pad21)") (class "Default")
      (node (ref "U$3") (pin "21") (pinfunction "21_21") (pintype "bidirectional"))
    )
    (net (code "78") (name "unconnected-(U$3-Pad22)") (class "Default")
      (node (ref "U$3") (pin "22") (pinfunction "22_22") (pintype "bidirectional"))
    )
    (net (code "79") (name "unconnected-(U$3-Pad23)") (class "Default")
      (node (ref "U$3") (pin "23") (pinfunction "23_23") (pintype "bidirectional"))
    )
    (net (code "80") (name "unconnected-(U$3-Pad24)") (class "Default")
      (node (ref "U$3") (pin "24") (pinfunction "24_24") (pintype "bidirectional"))
    )
    (net (code "81") (name "unconnected-(U$3-Pad25)") (class "Default")
      (node (ref "U$3") (pin "25") (pinfunction "25_25") (pintype "bidirectional"))
    )
    (net (code "82") (name "unconnected-(U$3-Pad26)") (class "Default")
      (node (ref "U$3") (pin "26") (pinfunction "26_26") (pintype "bidirectional"))
    )
    (net (code "83") (name "unconnected-(U$3-Pad33)") (class "Default")
      (node (ref "U$3") (pin "33") (pinfunction "33_33") (pintype "bidirectional"))
    )
    (net (code "84") (name "unconnected-(U$3-Pad34)") (class "Default")
      (node (ref "U$3") (pin "34") (pinfunction "34_34") (pintype "bidirectional"))
    )
    (net (code "85") (name "unconnected-(U$3-Pad35)") (class "Default")
      (node (ref "U$3") (pin "35") (pinfunction "35_35") (pintype "bidirectional"))
    )
    (net (code "86") (name "unconnected-(U$3-Pad36)") (class "Default")
      (node (ref "U$3") (pin "36") (pinfunction "36_36") (pintype "bidirectional"))
    )
    (net (code "87") (name "unconnected-(U$3-Pad37)") (class "Default")
      (node (ref "U$3") (pin "37") (pinfunction "37_37") (pintype "bidirectional"))
    )
    (net (code "88") (name "unconnected-(U$3-Pad38)") (class "Default")
      (node (ref "U$3") (pin "38") (pinfunction "38_38") (pintype "bidirectional"))
    )
    (net (code "89") (name "unconnected-(U$3-Pad39)") (class "Default")
      (node (ref "U$3") (pin "39") (pinfunction "39_39") (pintype "bidirectional"))
    )
    (net (code "90") (name "unconnected-(U$3-Pad40)") (class "Default")
      (node (ref "U$3") (pin "40") (pinfunction "40_40") (pintype "bidirectional"))
    )
    (net (code "91") (name "unconnected-(U$3-Pad41)") (class "Default")
      (node (ref "U$3") (pin "41") (pinfunction "41_41") (pintype "bidirectional"))
    )
    (net (code "92") (name "unconnected-(U$3-Pad42)") (class "Default")
      (node (ref "U$3") (pin "42") (pinfunction "42_42") (pintype "bidirectional"))
    )
    (net (code "93") (name "unconnected-(U$3-Pad43)") (class "Default")
      (node (ref "U$3") (pin "43") (pinfunction "43_43") (pintype "bidirectional"))
    )
    (net (code "94") (name "unconnected-(U$3-Pad44)") (class "Default")
      (node (ref "U$3") (pin "44") (pinfunction "44_44") (pintype "bidirectional"))
    )
    (net (code "95") (name "unconnected-(U$3-Pad45)") (class "Default")
      (node (ref "U$3") (pin "45") (pinfunction "45_45") (pintype "bidirectional"))
    )
    (net (code "96") (name "unconnected-(U$3-Pad46)") (class "Default")
      (node (ref "U$3") (pin "46") (pinfunction "46_46") (pintype "bidirectional"))
    )
    (net (code "97") (name "unconnected-(U$3-Pad47)") (class "Default")
      (node (ref "U$3") (pin "47") (pinfunction "47_47") (pintype "bidirectional"))
    )
    (net (code "98") (name "unconnected-(U$3-Pad48)") (class "Default")
      (node (ref "U$3") (pin "48") (pinfunction "48_48") (pintype "bidirectional"))
    )
    (net (code "99") (name "unconnected-(U$3-Pad49)") (class "Default")
      (node (ref "U$3") (pin "49") (pinfunction "49_49") (pintype "bidirectional"))
    )
    (net (code "100") (name "unconnected-(U$3-Pad50)") (class "Default")
      (node (ref "U$3") (pin "50") (pinfunction "50_50") (pintype "bidirectional"))
    )
    (net (code "101") (name "unconnected-(U$3-Pad51)") (class "Default")
      (node (ref "U$3") (pin "51") (pinfunction "51_51") (pintype "bidirectional"))
    )
    (net (code "102") (name "unconnected-(U$3-Pad52)") (class "Default")
      (node (ref "U$3") (pin "52") (pinfunction "52_52") (pintype "bidirectional"))
    )
    (net (code "103") (name "unconnected-(U$3-Pad79)") (class "Default")
      (node (ref "U$3") (pin "79") (pinfunction "79_79") (pintype "bidirectional"))
    )
    (net (code "104") (name "unconnected-(U$3-Pad80)") (class "Default")
      (node (ref "U$3") (pin "80") (pinfunction "80_80") (pintype "bidirectional"))
    )
    (net (code "105") (name "unconnected-(U$3-Pad81)") (class "Default")
      (node (ref "U$3") (pin "81") (pinfunction "81_81") (pintype "bidirectional"))
    )
    (net (code "106") (name "unconnected-(U$3-Pad82)") (class "Default")
      (node (ref "U$3") (pin "82") (pinfunction "82_82") (pintype "bidirectional"))
    )
    (net (code "107") (name "unconnected-(U$3-Pad83)") (class "Default")
      (node (ref "U$3") (pin "83") (pinfunction "83_83") (pintype "bidirectional"))
    )
    (net (code "108") (name "unconnected-(U$3-Pad84)") (class "Default")
      (node (ref "U$3") (pin "84") (pinfunction "84_84") (pintype "bidirectional"))
    )
    (net (code "109") (name "unconnected-(U$3-Pad85)") (class "Default")
      (node (ref "U$3") (pin "85") (pinfunction "85_85") (pintype "bidirectional"))
    )
    (net (code "110") (name "unconnected-(U$3-Pad86)") (class "Default")
      (node (ref "U$3") (pin "86") (pinfunction "86_86") (pintype "bidirectional"))
    )
    (net (code "111") (name "unconnected-(U$3-Pad87)") (class "Default")
      (node (ref "U$3") (pin "87") (pinfunction "87_87") (pintype "bidirectional"))
    )
    (net (code "112") (name "unconnected-(U$3-Pad88)") (class "Default")
      (node (ref "U$3") (pin "88") (pinfunction "88_88") (pintype "bidirectional"))
    )
    (net (code "113") (name "unconnected-(U$3-Pad89)") (class "Default")
      (node (ref "U$3") (pin "89") (pinfunction "89_89") (pintype "bidirectional"))
    )
    (net (code "114") (name "unconnected-(U$3-Pad90)") (class "Default")
      (node (ref "U$3") (pin "90") (pinfunction "90_90") (pintype "bidirectional"))
    )
    (net (code "115") (name "unconnected-(U$3-Pad91)") (class "Default")
      (node (ref "U$3") (pin "91") (pinfunction "91_91") (pintype "bidirectional"))
    )
    (net (code "116") (name "unconnected-(U$3-Pad92)") (class "Default")
      (node (ref "U$3") (pin "92") (pinfunction "92_92") (pintype "bidirectional"))
    )
    (net (code "117") (name "unconnected-(U$3-Pad93)") (class "Default")
      (node (ref "U$3") (pin "93") (pinfunction "93_93") (pintype "bidirectional"))
    )
    (net (code "118") (name "unconnected-(U$3-Pad94)") (class "Default")
      (node (ref "U$3") (pin "94") (pinfunction "94_94") (pintype "bidirectional"))
    )
    (net (code "119") (name "unconnected-(U$3-Pad95)") (class "Default")
      (node (ref "U$3") (pin "95") (pinfunction "95_95") (pintype "bidirectional"))
    )
    (net (code "120") (name "unconnected-(U$3-Pad96)") (class "Default")
      (node (ref "U$3") (pin "96") (pinfunction "96_96") (pintype "bidirectional"))
    )
    (net (code "121") (name "unconnected-(U$3-Pad97)") (class "Default")
      (node (ref "U$3") (pin "97") (pinfunction "97_97") (pintype "bidirectional"))
    )
    (net (code "122") (name "unconnected-(U$3-Pad98)") (class "Default")
      (node (ref "U$3") (pin "98") (pinfunction "98_98") (pintype "bidirectional"))
    )
    (net (code "123") (name "unconnected-(U$3-Pad99)") (class "Default")
      (node (ref "U$3") (pin "99") (pinfunction "99_99") (pintype "bidirectional"))
    )
    (net (code "124") (name "unconnected-(U$3-Pad100)") (class "Default")
      (node (ref "U$3") (pin "100") (pinfunction "100_100") (pintype "bidirectional"))
    )
    (net (code "125") (name "unconnected-(U$3-Pad101)") (class "Default")
      (node (ref "U$3") (pin "101") (pinfunction "101_101") (pintype "bidirectional"))
    )
    (net (code "126") (name "unconnected-(U$3-Pad102)") (class "Default")
      (node (ref "U$3") (pin "102") (pinfunction "102_102") (pintype "bidirectional"))
    )
    (net (code "127") (name "unconnected-(U$3-Pad103)") (class "Default")
      (node (ref "U$3") (pin "103") (pinfunction "103_103") (pintype "bidirectional"))
    )
    (net (code "128") (name "unconnected-(U$3-Pad104)") (class "Default")
      (node (ref "U$3") (pin "104") (pinfunction "104_104") (pintype "bidirectional"))
    )
    (net (code "129") (name "unconnected-(U2-*FAULT-Pad5)") (class "Default")
      (node (ref "U2") (pin "5") (pinfunction "*FAULT_5") (pintype "output"))
    )
    (net (code "130") (name "unconnected-(U2-EPAD-Pad13)") (class "Default")
      (node (ref "U2") (pin "13") (pinfunction "EPAD_13") (pintype "passive"))
    )
    (net (code "131") (name "unconnected-(U2-TIMER-Pad6)") (class "Default")
      (node (ref "U2") (pin "6") (pinfunction "TIMER_6") (pintype "passive"))
    )
    (net (code "132") (name "unconnected-(U3-BOOT0-Pad44)") (class "Default")
      (node (ref "U3") (pin "44") (pinfunction "BOOT0_44") (pintype "bidirectional"))
    )
    (net (code "133") (name "unconnected-(U3-NRST-Pad7)") (class "Default")
      (node (ref "U3") (pin "7") (pinfunction "NRST_7") (pintype "bidirectional"))
    )
    (net (code "134") (name "unconnected-(U3-PA4-Pad14)") (class "Default")
      (node (ref "U3") (pin "14") (pinfunction "PA4_14") (pintype "bidirectional"))
    )
    (net (code "135") (name "unconnected-(U3-PA8-Pad45)") (class "Default")
      (node (ref "U3") (pin "45") (pinfunction "PA8_45") (pintype "bidirectional"))
    )
    (net (code "136") (name "unconnected-(U3-PA9-Pad46)") (class "Default")
      (node (ref "U3") (pin "46") (pinfunction "PA9_46") (pintype "bidirectional"))
    )
    (net (code "137") (name "unconnected-(U3-PA10-Pad31)") (class "Default")
      (node (ref "U3") (pin "31") (pinfunction "PA10_31") (pintype "bidirectional"))
    )
    (net (code "138") (name "unconnected-(U3-PA11-Pad32)") (class "Default")
      (node (ref "U3") (pin "32") (pinfunction "PA11_32") (pintype "bidirectional"))
    )
    (net (code "139") (name "unconnected-(U3-PA12-Pad33)") (class "Default")
      (node (ref "U3") (pin "33") (pinfunction "PA12_33") (pintype "bidirectional"))
    )
    (net (code "140") (name "unconnected-(U3-PA15{slash}JTDI-Pad38)") (class "Default")
      (node (ref "U3") (pin "38") (pinfunction "PA15/JTDI_38") (pintype "bidirectional"))
    )
    (net (code "141") (name "unconnected-(U3-PB2{slash}BOOT-Pad20)") (class "Default")
      (node (ref "U3") (pin "20") (pinfunction "PB2/BOOT_20") (pintype "bidirectional"))
    )
    (net (code "142") (name "unconnected-(U3-PB3{slash}JTDO-Pad39)") (class "Default")
      (node (ref "U3") (pin "39") (pinfunction "PB3/JTDO_39") (pintype "bidirectional"))
    )
    (net (code "143") (name "unconnected-(U3-PB4{slash}JNTRST-Pad40)") (class "Default")
      (node (ref "U3") (pin "40") (pinfunction "PB4/JNTRST_40") (pintype "bidirectional"))
    )
    (net (code "144") (name "unconnected-(U3-PB5-Pad41)") (class "Default")
      (node (ref "U3") (pin "41") (pinfunction "PB5_41") (pintype "bidirectional"))
    )
    (net (code "145") (name "unconnected-(U3-PB6-Pad42)") (class "Default")
      (node (ref "U3") (pin "42") (pinfunction "PB6_42") (pintype "bidirectional"))
    )
    (net (code "146") (name "unconnected-(U3-PB10-Pad21)") (class "Default")
      (node (ref "U3") (pin "21") (pinfunction "PB10_21") (pintype "bidirectional"))
    )
    (net (code "147") (name "unconnected-(U3-PB12-Pad25)") (class "Default")
      (node (ref "U3") (pin "25") (pinfunction "PB12_25") (pintype "bidirectional"))
    )
    (net (code "148") (name "unconnected-(U3-PB13-Pad26)") (class "Default")
      (node (ref "U3") (pin "26") (pinfunction "PB13_26") (pintype "bidirectional"))
    )
    (net (code "149") (name "unconnected-(U3-PB14-Pad27)") (class "Default")
      (node (ref "U3") (pin "27") (pinfunction "PB14_27") (pintype "bidirectional"))
    )
    (net (code "150") (name "unconnected-(U3-PB15-Pad28)") (class "Default")
      (node (ref "U3") (pin "28") (pinfunction "PB15_28") (pintype "bidirectional"))
    )
    (net (code "151") (name "unconnected-(U3-PC14-Pad3)") (class "Default")
      (node (ref "U3") (pin "3") (pinfunction "PC14_3") (pintype "bidirectional"))
    )
    (net (code "152") (name "unconnected-(U3-VBAT-Pad1)") (class "Default")
      (node (ref "U3") (pin "1") (pinfunction "VBAT_1") (pintype "bidirectional"))
    )
  )
)
